# Motorsteuerung_V5.net
KiCad netlist of a schematic drawn in Altium Designer
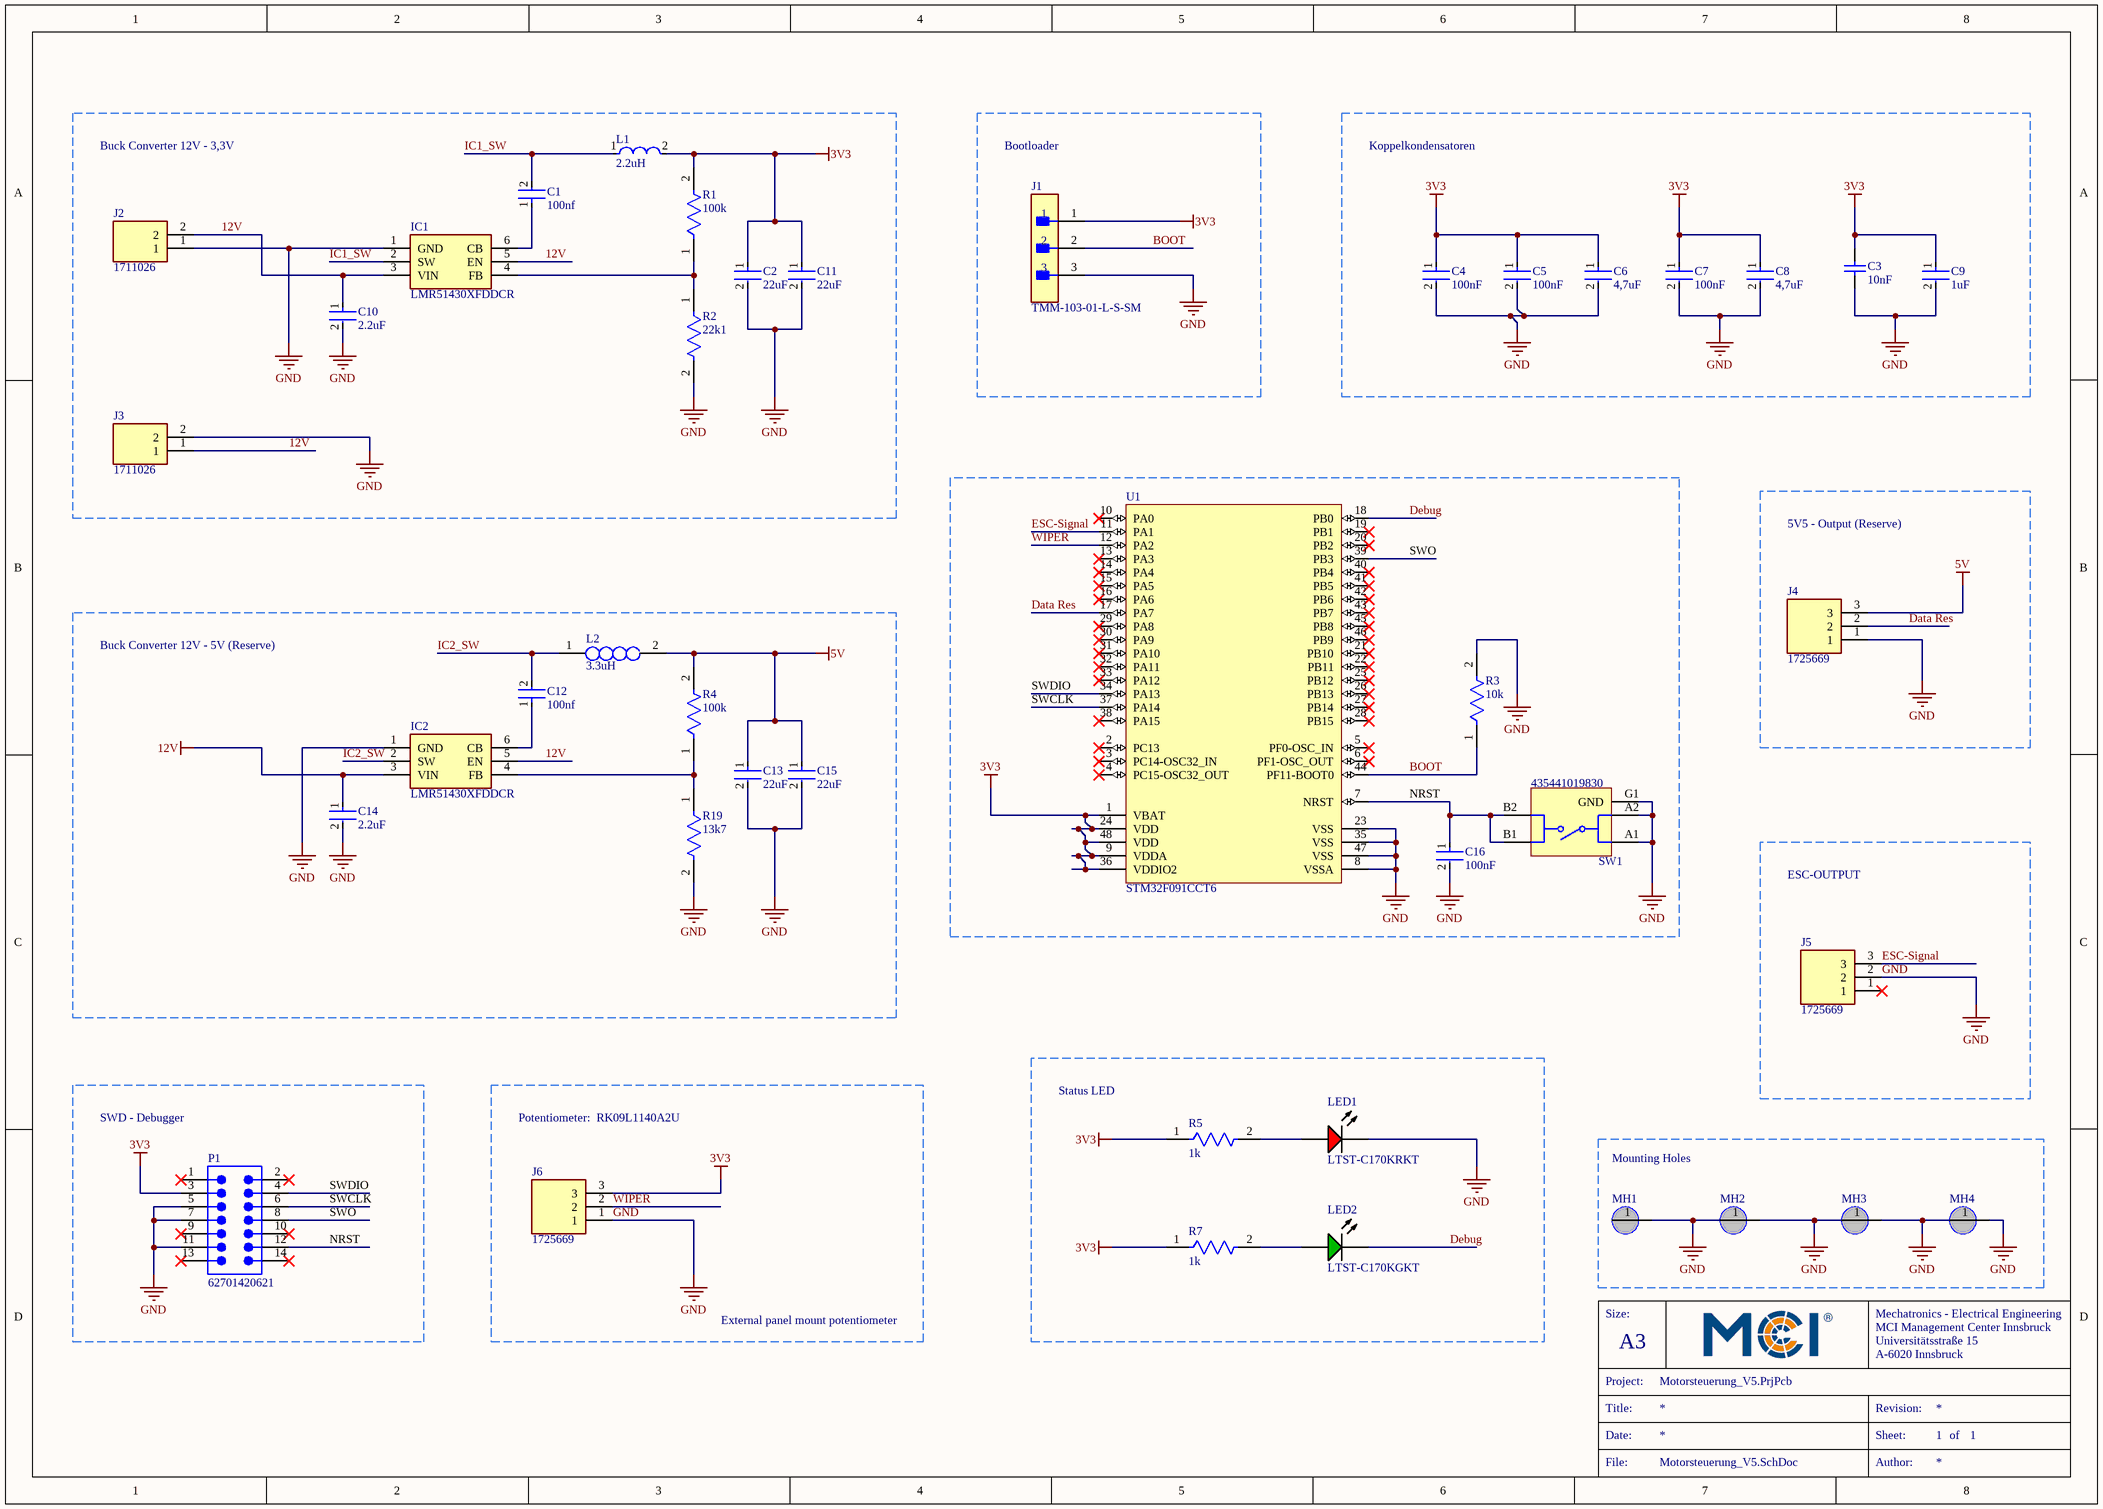
[diagram p0: Motorsteuerung_V5.SchDoc]

(export (version "E")
  (design (tool "Eeschema 10.0.6"))
  (components
    (comp (ref "C1")
      (value "100nf")
      (footprint "FP-C0805C104M5UACTU-MFG")
      (description "CAP CER 0.1UF 50V Z5U 0805")
      (fields (field (name "TOLERANCE") "20%") (field (name "VOLTAGE") "50V"))
      (libsource (lib "Altium Content Vault") (part "b4654b650e69147ec39a6b967a45e02"))
    )
    (comp (ref "C2")
      (value "22uF")
      (footprint "FP-C1210C226K4RACTU-MFG")
      (description "CAP CER 22UF 16V X7R 1210")
      (fields (field (name "VOLTAGE") "16V") (field (name "TOLERANCE") "10%"))
      (libsource (lib "Altium Content Vault") (part "b4654b650e69147ec39a6b967a45e02"))
    )
    (comp (ref "C3")
      (value "10nF")
      (footprint "CAPC1608X92X38ML15T08")
      (fields (field (name "MANUFACTURER") "Vitramon") (field (name "PART NUMBER") "VJ0603Y103KXJAC"))
      (libsource (lib "Altium Content Vault") (part "CAP"))
    )
    (comp (ref "C4")
      (value "100nF")
      (footprint "FP-CC0603-DA-MFG")
      (description "CAP CER 0.1UF 25V X7R 0603")
      (fields
        (field (name "MANUFACTURER") "YAGEO")
        (field (name "OCTOPART") "https://octopart.com/cc0603krx7r8bb104-yageo-8376534")
      )
      (libsource (lib "Altium Content Vault") (part "11868f565c42a9108669ba33697ecf6"))
    )
    (comp (ref "C5")
      (value "100nF")
      (footprint "FP-CC0603-DA-MFG")
      (description "CAP CER 0.1UF 25V X7R 0603")
      (fields
        (field (name "MANUFACTURER") "YAGEO")
        (field (name "OCTOPART") "https://octopart.com/cc0603krx7r8bb104-yageo-8376534")
      )
      (libsource (lib "Altium Content Vault") (part "11868f565c42a9108669ba33697ecf6"))
    )
    (comp (ref "C6")
      (value "4,7uF")
      (footprint "FP-CC0603-DA-MFG")
      (description "CAP CER 4.7UF 16V X5R 0603")
      (fields
        (field (name "MANUFACTURER") "YAGEO")
        (field (name "MANUFACTURER PART NUMBER") "CC0603KRX5R7BB475")
      )
      (libsource (lib "Altium Content Vault") (part "11868f565c42a9108669ba33697ecf6"))
    )
    (comp (ref "C7")
      (value "100nF")
      (footprint "FP-CC0603-DA-MFG")
      (description "CAP CER 0.1UF 25V X7R 0603")
      (fields
        (field (name "MANUFACTURER") "YAGEO")
        (field (name "OCTOPART") "https://octopart.com/cc0603krx7r8bb104-yageo-8376534")
      )
      (libsource (lib "Altium Content Vault") (part "11868f565c42a9108669ba33697ecf6"))
    )
    (comp (ref "C8")
      (value "4,7uF")
      (footprint "FP-CC0603-DA-MFG")
      (description "CAP CER 4.7UF 16V X5R 0603")
      (fields
        (field (name "MANUFACTURER") "YAGEO")
        (field (name "MANUFACTURER PART NUMBER") "CC0603KRX5R7BB475")
      )
      (libsource (lib "Altium Content Vault") (part "11868f565c42a9108669ba33697ecf6"))
    )
    (comp (ref "C9")
      (value "1uF")
      (footprint "FP-CC0603-DA-MFG")
      (description "CAP CER 1UF 16V X5R 0603")
      (fields
        (field (name "OCTOPART") "https://octopart.com/cc0603krx5r7bb105-yageo-8376530")
        (field (name "MANUFACTURER PART NUMBER") "CC0603KRX5R7BB105")
      )
      (libsource (lib "Altium Content Vault") (part "11868f565c42a9108669ba33697ecf6"))
    )
    (comp (ref "C10")
      (value "2.2uF")
      (footprint "FP-CC1210-G3-MFG")
      (description "CAP CER 1210")
      (fields (field (name "TOLERANCE") "10%"))
      (libsource (lib "Altium Content Vault") (part "b4654b650e69147ec39a6b967a45e02"))
    )
    (comp (ref "C11")
      (value "22uF")
      (footprint "FP-C1210C226K4RACTU-MFG")
      (description "CAP CER 22UF 16V X7R 1210")
      (fields (field (name "VOLTAGE") "16V") (field (name "TOLERANCE") "10%"))
      (libsource (lib "Altium Content Vault") (part "b4654b650e69147ec39a6b967a45e02"))
    )
    (comp (ref "C12")
      (value "100nf")
      (footprint "FP-C0805C104M5UACTU-MFG")
      (description "CAP CER 0.1UF 50V Z5U 0805")
      (fields (field (name "TOLERANCE") "20%") (field (name "VOLTAGE") "50V"))
      (libsource (lib "Altium Content Vault") (part "b4654b650e69147ec39a6b967a45e02"))
    )
    (comp (ref "C13")
      (value "22uF")
      (footprint "FP-C1210C226K4RACTU-MFG")
      (description "CAP CER 22UF 16V X7R 1210")
      (fields (field (name "VOLTAGE") "16V") (field (name "TOLERANCE") "10%"))
      (libsource (lib "Altium Content Vault") (part "b4654b650e69147ec39a6b967a45e02"))
    )
    (comp (ref "C14")
      (value "2.2uF")
      (footprint "FP-CC1210-G3-MFG")
      (description "CAP CER 1210")
      (fields (field (name "TOLERANCE") "10%"))
      (libsource (lib "Altium Content Vault") (part "b4654b650e69147ec39a6b967a45e02"))
    )
    (comp (ref "C15")
      (value "22uF")
      (footprint "FP-C1210C226K4RACTU-MFG")
      (description "CAP CER 22UF 16V X7R 1210")
      (fields (field (name "VOLTAGE") "16V") (field (name "TOLERANCE") "10%"))
      (libsource (lib "Altium Content Vault") (part "b4654b650e69147ec39a6b967a45e02"))
    )
    (comp (ref "C16")
      (value "100nF")
      (footprint "FP-CC0805-EB-MFG")
      (description "CC0805KKX7RYBB104 Capacitor Ceramic 0.01uF 250V X7R 10% 0805 T/R")
      (fields (field (name "TOLERANCE") "10%"))
      (libsource (lib "Altium Content Vault") (part "b4654b650e69147ec39a6b967a45e02"))
    )
    (comp (ref "IC1")
      (value "LMR51430XFDDCR")
      (footprint "SamacSys:SOT95P280X110-6N")
      (description "Integrated Circuit")
      (fields (field (name "MOUSER PART NUMBER") "595-LMR51430XFDDCR"))
      (libsource (lib "*") (part "LMR51430XFDDCR"))
    )
    (comp (ref "IC2")
      (value "LMR51430XFDDCR")
      (footprint "SamacSys:SOT95P280X110-6N")
      (description "Integrated Circuit")
      (fields (field (name "MOUSER PART NUMBER") "595-LMR51430XFDDCR"))
      (libsource (lib "*") (part "LMR51430XFDDCR"))
    )
    (comp (ref "J1")
      (value "TMM-103-01-L-S-SM")
      (footprint "FP-TMM-103-01-L-S-SM-MFG")
      (description "CONN HEADER SMD 3POS 2MM")
      (libsource (lib "Altium Content Vault") (part "0d3f023dd272f625e17a2be33dea85f"))
    )
    (comp (ref "J2")
      (value "1711026")
      (footprint "SamacSys:1711026")
      (description "Connector")
      (fields (field (name "MOUSER PART NUMBER") "651-1711026"))
      (libsource (lib "*") (part "1711026"))
    )
    (comp (ref "J3")
      (value "1711026")
      (footprint "SamacSys:1711026")
      (description "Connector")
      (fields (field (name "MOUSER PART NUMBER") "651-1711026"))
      (libsource (lib "*") (part "1711026"))
    )
    (comp (ref "J4")
      (value "1725669")
      (footprint "SamacSys:1725669")
      (description "Connector")
      (fields (field (name "MOUSER PART NUMBER") "651-1725669"))
      (libsource (lib "Motorsteuerung_V5") (part "1725669"))
    )
    (comp (ref "J5")
      (value "1725669")
      (footprint "SamacSys:1725669")
      (description "Connector")
      (fields (field (name "MOUSER PART NUMBER") "651-1725669"))
      (libsource (lib "Motorsteuerung_V5") (part "1725669"))
    )
    (comp (ref "J6")
      (value "1725669")
      (footprint "SamacSys:1725669")
      (description "Connector")
      (fields (field (name "MOUSER PART NUMBER") "651-1725669"))
      (libsource (lib "Motorsteuerung_V5") (part "1725669"))
    )
    (comp (ref "L1")
      (value "2.2uH")
      (footprint "FP-IHLP-2020BZ-FP_1_905x2-MFG")
      (description "Fixed Inductors Commercial Low DCR Series 2.2uH 5A 37.7mΩ 20%")
      (fields (field (name "TOLERANCE") "20%"))
      (libsource (lib "Altium Content Vault") (part "725321dda6339637d4d059423bc1c3c"))
    )
    (comp (ref "L2")
      (value "3.3uH")
      (footprint "SamacSys:INDPM6054X300N")
      (description "Inductor")
      (fields
        (field (name "MANUFACTURER_PART_NUMBER") "PA4340.332NLT")
        (field (name "MOUSER PART NUMBER") "673-PA4340.332NLT")
      )
      (libsource (lib "*") (part "PA4340.332NLT"))
    )
    (comp (ref "LED1")
      (value "LTST-C170KRKT")
      (footprint "LTST-C170KRKT_V")
      (description "LED Red, 75 mW, 54 mcd, -55 to 85 degC, 2-Pin SMD, RoHS, Tape and Reel")
      (fields (field (name "MANUFACTURER") "Lite-On"))
      (libsource (lib "Altium Content Vault") (part "LED-RED-AK-2"))
    )
    (comp (ref "LED2")
      (value "LTST-C170KGKT")
      (footprint "LTST-LTST-C170KGKT-2_V")
      (description "Ultra Bright AlInGaP Chip LED, 75 mW, -55 to 85 degC, 2-Pin SMD (0805), RoHS, Tape and Reel")
      (fields (field (name "MANUFACTURER") "Lite-On"))
      (libsource (lib "Altium Content Vault") (part "LED-GREEN-KA-2"))
    )
    (comp (ref "MH1")
      (value "MountingHole")
      (footprint "MTH")
      (libsource (lib "Motorsteuerung_V5") (part "MountingHole"))
    )
    (comp (ref "MH2")
      (value "MountingHole")
      (footprint "MTH")
      (libsource (lib "Motorsteuerung_V5") (part "MountingHole"))
    )
    (comp (ref "MH3")
      (value "MountingHole")
      (footprint "MTH")
      (libsource (lib "Motorsteuerung_V5") (part "MountingHole"))
    )
    (comp (ref "MH4")
      (value "MountingHole")
      (footprint "MTH")
      (libsource (lib "Motorsteuerung_V5") (part "MountingHole"))
    )
    (comp (ref "P1")
      (value "62701420621")
      (footprint "62701420621")
      (description "Conn, Hdr, 14Pos, 2Row, 1.27Mm, Smt Rohs Compliant: Yes")
      (libsource (lib "Altium Content Vault") (part "Header_Male_2R_14P"))
    )
    (comp (ref "R1")
      (value "100k")
      (footprint "FP-RQ73C2A-IPC_B")
      (description "RQ73 0805 100KΩ 0.2W 10ppm/°C 0.1% 100V")
      (libsource (lib "Altium Content Vault") (part "1029c3af85768c4190bb7ad29bc67b5"))
    )
    (comp (ref "R2")
      (value "22k1")
      (footprint "FP-RT0805-MFG")
      (description "RES SMD 22.1K OHM 0.1% 1/8W 0805")
      (fields
        (field (name "MANUFACTURER PART NUMBER") "RT0805BRD0722K1L")
        (field (name "MANUFACTURER") "Yageo")
      )
      (libsource (lib "Altium Content Vault") (part "1029c3af85768c4190bb7ad29bc67b5"))
    )
    (comp (ref "R3")
      (value "10k")
      (footprint "FP-CRGCQ0805-IPC_C")
      (description "CRGCQ 0805 10K 5%")
      (fields
        (field (name "MANUFACTURER PART NUMBER") "CRGCQ0805J10K")
        (field (name "MANUFACTURER") "TE Connectivity")
      )
      (libsource (lib "Altium Content Vault") (part "1029c3af85768c4190bb7ad29bc67b5"))
    )
    (comp (ref "R4")
      (value "100k")
      (footprint "FP-RQ73C2A-IPC_B")
      (description "RQ73 0805 100KΩ 0.2W 10ppm/°C 0.1% 100V")
      (libsource (lib "Altium Content Vault") (part "1029c3af85768c4190bb7ad29bc67b5"))
    )
    (comp (ref "R5")
      (value "1k")
      (footprint "FP-CRGCQ0805-IPC_C")
      (description "CRGCQ 0805 1K0 1%")
      (fields
        (field (name "OCTOPART") "https://octopart.com/crgcq0805f1k0-te+connectivity-91018154")
        (field (name "MANUFACTURER") "TE Connectivity")
      )
      (libsource (lib "Altium Content Vault") (part "1029c3af85768c4190bb7ad29bc67b5"))
    )
    (comp (ref "R7")
      (value "1k")
      (footprint "FP-CRGCQ0805-IPC_C")
      (description "CRGCQ 0805 1K0 1%")
      (fields
        (field (name "OCTOPART") "https://octopart.com/crgcq0805f1k0-te+connectivity-91018154")
        (field (name "MANUFACTURER") "TE Connectivity")
      )
      (libsource (lib "Altium Content Vault") (part "1029c3af85768c4190bb7ad29bc67b5"))
    )
    (comp (ref "R19")
      (value "13k7")
      (footprint "FP-RT0805-MFG")
      (description "RES 13.7K OHM 1/8W .1% SMD 0805")
      (fields
        (field (name "MANUFACTURER PART NUMBER") "RT0805BRD0713K7L")
        (field (name "MANUFACTURER") "Yageo")
      )
      (libsource (lib "Altium Content Vault") (part "1029c3af85768c4190bb7ad29bc67b5"))
    )
    (comp (ref "SW1")
      (value "435441019830")
      (footprint "435441019830")
      (description "Tactile Switch, 0.05A, 32Vdc, Smd, 300Gf Rohs Compliant: Yes")
      (libsource (lib "Altium Content Vault") (part "SPST-NO_4P_1GND"))
    )
    (comp (ref "U1")
      (value "STM32F091CCT6")
      (footprint "LQFP48_M")
      (fields (field (name "MANUFACTURER") "STMicroelectronics"))
      (libsource (lib "Altium Content Vault") (part "STM-STM32F091C-LQFP-48"))
    )
  )
  (nets
    (net (code "1") (name "/BOOT") (class "Default")
      (node (ref "J1") (pin "2") (pinfunction "2_2") (pintype "passive"))
      (node (ref "R3") (pin "1") (pinfunction "1_1") (pintype "passive"))
      (node (ref "U1") (pin "44") (pinfunction "PF11-BOOT0_44") (pintype "bidirectional"))
    )
    (net (code "2") (name "/Data Res") (class "Default")
      (node (ref "J4") (pin "2") (pinfunction "2_2") (pintype "passive"))
      (node (ref "U1") (pin "17") (pinfunction "PA7_17") (pintype "bidirectional"))
    )
    (net (code "3") (name "/Debug") (class "Default")
      (node (ref "LED2") (pin "1") (pinfunction "K_1") (pintype "passive"))
      (node (ref "U1") (pin "18") (pinfunction "PB0_18") (pintype "bidirectional"))
    )
    (net (code "4") (name "/ESC-Signal") (class "Default")
      (node (ref "J5") (pin "3") (pinfunction "3_3") (pintype "passive"))
      (node (ref "U1") (pin "11") (pinfunction "PA1_11") (pintype "bidirectional"))
    )
    (net (code "5") (name "/IC1_SW") (class "Default")
      (node (ref "C1") (pin "2") (pinfunction "2_2") (pintype "passive"))
      (node (ref "IC1") (pin "2") (pinfunction "SW_2") (pintype "passive"))
      (node (ref "L1") (pin "1") (pinfunction "1_1") (pintype "passive"))
    )
    (net (code "6") (name "/IC2_SW") (class "Default")
      (node (ref "C12") (pin "2") (pinfunction "2_2") (pintype "passive"))
      (node (ref "IC2") (pin "2") (pinfunction "SW_2") (pintype "passive"))
      (node (ref "L2") (pin "1") (pinfunction "1_1") (pintype "passive"))
    )
    (net (code "7") (name "/NRST") (class "Default")
      (node (ref "C16") (pin "1") (pinfunction "1_1") (pintype "passive"))
      (node (ref "P1") (pin "12") (pinfunction "12_12") (pintype "passive"))
      (node (ref "SW1") (pin "B1") (pinfunction "B1_B1") (pintype "passive"))
      (node (ref "SW1") (pin "B2") (pinfunction "B2_B2") (pintype "passive"))
      (node (ref "U1") (pin "7") (pinfunction "NRST_7") (pintype "bidirectional"))
    )
    (net (code "8") (name "/SWCLK") (class "Default")
      (node (ref "P1") (pin "6") (pinfunction "6_6") (pintype "passive"))
      (node (ref "U1") (pin "37") (pinfunction "PA14_37") (pintype "bidirectional"))
    )
    (net (code "9") (name "/SWDIO") (class "Default")
      (node (ref "P1") (pin "4") (pinfunction "4_4") (pintype "passive"))
      (node (ref "U1") (pin "34") (pinfunction "PA13_34") (pintype "bidirectional"))
    )
    (net (code "10") (name "/SWO") (class "Default")
      (node (ref "P1") (pin "8") (pinfunction "8_8") (pintype "passive"))
      (node (ref "U1") (pin "39") (pinfunction "PB3_39") (pintype "bidirectional"))
    )
    (net (code "11") (name "/WIPER") (class "Default")
      (node (ref "J6") (pin "2") (pinfunction "2_2") (pintype "passive"))
      (node (ref "U1") (pin "12") (pinfunction "PA2_12") (pintype "bidirectional"))
    )
    (net (code "12") (name "3V3") (class "Default")
      (node (ref "C11") (pin "1") (pinfunction "1_1") (pintype "passive"))
      (node (ref "C2") (pin "1") (pinfunction "1_1") (pintype "passive"))
      (node (ref "C3") (pin "2") (pinfunction "2_2") (pintype "passive"))
      (node (ref "C4") (pin "1") (pinfunction "1_1") (pintype "passive"))
      (node (ref "C5") (pin "1") (pinfunction "1_1") (pintype "passive"))
      (node (ref "C6") (pin "1") (pinfunction "1_1") (pintype "passive"))
      (node (ref "C7") (pin "1") (pinfunction "1_1") (pintype "passive"))
      (node (ref "C8") (pin "1") (pinfunction "1_1") (pintype "passive"))
      (node (ref "C9") (pin "1") (pinfunction "1_1") (pintype "passive"))
      (node (ref "J1") (pin "1") (pinfunction "1_1") (pintype "passive"))
      (node (ref "J6") (pin "3") (pinfunction "3_3") (pintype "passive"))
      (node (ref "L1") (pin "2") (pinfunction "2_2") (pintype "passive"))
      (node (ref "P1") (pin "3") (pinfunction "3_3") (pintype "passive"))
      (node (ref "R1") (pin "2") (pinfunction "2_2") (pintype "passive"))
      (node (ref "R5") (pin "1") (pinfunction "1_1") (pintype "passive"))
      (node (ref "R7") (pin "1") (pinfunction "1_1") (pintype "passive"))
      (node (ref "U1") (pin "1") (pinfunction "VBAT_1") (pintype "power_in"))
      (node (ref "U1") (pin "24") (pinfunction "VDD_24") (pintype "power_in"))
      (node (ref "U1") (pin "36") (pinfunction "VDDIO2_36") (pintype "power_in"))
      (node (ref "U1") (pin "48") (pinfunction "VDD_48") (pintype "power_in"))
      (node (ref "U1") (pin "9") (pinfunction "VDDA_9") (pintype "power_in"))
    )
    (net (code "13") (name "5V") (class "Default")
      (node (ref "C13") (pin "1") (pinfunction "1_1") (pintype "passive"))
      (node (ref "C15") (pin "1") (pinfunction "1_1") (pintype "passive"))
      (node (ref "J4") (pin "3") (pinfunction "3_3") (pintype "passive"))
      (node (ref "L2") (pin "2") (pinfunction "2_2") (pintype "passive"))
      (node (ref "R4") (pin "2") (pinfunction "2_2") (pintype "passive"))
    )
    (net (code "14") (name "12V") (class "Default")
      (node (ref "C10") (pin "1") (pinfunction "1_1") (pintype "passive"))
      (node (ref "C14") (pin "1") (pinfunction "1_1") (pintype "passive"))
      (node (ref "IC1") (pin "3") (pinfunction "VIN_3") (pintype "passive"))
      (node (ref "IC1") (pin "5") (pinfunction "EN_5") (pintype "passive"))
      (node (ref "IC2") (pin "3") (pinfunction "VIN_3") (pintype "passive"))
      (node (ref "IC2") (pin "5") (pinfunction "EN_5") (pintype "passive"))
      (node (ref "J2") (pin "2") (pinfunction "2_2") (pintype "passive"))
      (node (ref "J3") (pin "1") (pinfunction "1_1") (pintype "passive"))
    )
    (net (code "15") (name "GND") (class "Default")
      (node (ref "C10") (pin "2") (pinfunction "2_2") (pintype "passive"))
      (node (ref "C11") (pin "2") (pinfunction "2_2") (pintype "passive"))
      (node (ref "C13") (pin "2") (pinfunction "2_2") (pintype "passive"))
      (node (ref "C14") (pin "2") (pinfunction "2_2") (pintype "passive"))
      (node (ref "C15") (pin "2") (pinfunction "2_2") (pintype "passive"))
      (node (ref "C16") (pin "2") (pinfunction "2_2") (pintype "passive"))
      (node (ref "C2") (pin "2") (pinfunction "2_2") (pintype "passive"))
      (node (ref "C3") (pin "1") (pinfunction "1_1") (pintype "passive"))
      (node (ref "C4") (pin "2") (pinfunction "2_2") (pintype "passive"))
      (node (ref "C5") (pin "2") (pinfunction "2_2") (pintype "passive"))
      (node (ref "C6") (pin "2") (pinfunction "2_2") (pintype "passive"))
      (node (ref "C7") (pin "2") (pinfunction "2_2") (pintype "passive"))
      (node (ref "C8") (pin "2") (pinfunction "2_2") (pintype "passive"))
      (node (ref "C9") (pin "2") (pinfunction "2_2") (pintype "passive"))
      (node (ref "IC1") (pin "1") (pinfunction "GND_1") (pintype "passive"))
      (node (ref "IC2") (pin "1") (pinfunction "GND_1") (pintype "passive"))
      (node (ref "J1") (pin "3") (pinfunction "3_3") (pintype "passive"))
      (node (ref "J2") (pin "1") (pinfunction "1_1") (pintype "passive"))
      (node (ref "J3") (pin "2") (pinfunction "2_2") (pintype "passive"))
      (node (ref "J4") (pin "1") (pinfunction "1_1") (pintype "passive"))
      (node (ref "J5") (pin "2") (pinfunction "2_2") (pintype "passive"))
      (node (ref "J6") (pin "1") (pinfunction "1_1") (pintype "passive"))
      (node (ref "LED1") (pin "2") (pinfunction "K_2") (pintype "passive"))
      (node (ref "MH1") (pin "1") (pintype "passive"))
      (node (ref "MH2") (pin "1") (pintype "passive"))
      (node (ref "MH3") (pin "1") (pintype "passive"))
      (node (ref "MH4") (pin "1") (pintype "passive"))
      (node (ref "P1") (pin "11") (pinfunction "11_11") (pintype "passive"))
      (node (ref "P1") (pin "5") (pinfunction "5_5") (pintype "passive"))
      (node (ref "P1") (pin "7") (pinfunction "7_7") (pintype "passive"))
      (node (ref "R19") (pin "2") (pinfunction "2_2") (pintype "passive"))
      (node (ref "R2") (pin "2") (pinfunction "2_2") (pintype "passive"))
      (node (ref "R3") (pin "2") (pinfunction "2_2") (pintype "passive"))
      (node (ref "SW1") (pin "A1") (pinfunction "A1_A1") (pintype "passive"))
      (node (ref "SW1") (pin "A2") (pinfunction "A2_A2") (pintype "passive"))
      (node (ref "SW1") (pin "G1") (pinfunction "GND_G1") (pintype "passive"))
      (node (ref "U1") (pin "23") (pinfunction "VSS_23") (pintype "power_in"))
      (node (ref "U1") (pin "35") (pinfunction "VSS_35") (pintype "power_in"))
      (node (ref "U1") (pin "47") (pinfunction "VSS_47") (pintype "power_in"))
      (node (ref "U1") (pin "8") (pinfunction "VSSA_8") (pintype "power_in"))
    )
    (net (code "16") (name "Net-(IC1-CB)") (class "Default")
      (node (ref "C1") (pin "1") (pinfunction "1_1") (pintype "passive"))
      (node (ref "IC1") (pin "6") (pinfunction "CB_6") (pintype "passive"))
    )
    (net (code "17") (name "Net-(IC1-FB)") (class "Default")
      (node (ref "IC1") (pin "4") (pinfunction "FB_4") (pintype "passive"))
      (node (ref "R1") (pin "1") (pinfunction "1_1") (pintype "passive"))
      (node (ref "R2") (pin "1") (pinfunction "1_1") (pintype "passive"))
    )
    (net (code "18") (name "Net-(IC2-CB)") (class "Default")
      (node (ref "C12") (pin "1") (pinfunction "1_1") (pintype "passive"))
      (node (ref "IC2") (pin "6") (pinfunction "CB_6") (pintype "passive"))
    )
    (net (code "19") (name "Net-(IC2-FB)") (class "Default")
      (node (ref "IC2") (pin "4") (pinfunction "FB_4") (pintype "passive"))
      (node (ref "R19") (pin "1") (pinfunction "1_1") (pintype "passive"))
      (node (ref "R4") (pin "1") (pinfunction "1_1") (pintype "passive"))
    )
    (net (code "20") (name "Net-(LED1-A)") (class "Default")
      (node (ref "LED1") (pin "1") (pinfunction "A_1") (pintype "passive"))
      (node (ref "R5") (pin "2") (pinfunction "2_2") (pintype "passive"))
    )
    (net (code "21") (name "Net-(LED2-A)") (class "Default")
      (node (ref "LED2") (pin "2") (pinfunction "A_2") (pintype "passive"))
      (node (ref "R7") (pin "2") (pinfunction "2_2") (pintype "passive"))
    )
    (net (code "22") (name "unconnected-(J5-Pad1)") (class "Default")
      (node (ref "J5") (pin "1") (pinfunction "1_1") (pintype "passive+no_connect"))
    )
    (net (code "23") (name "unconnected-(P1-Pad1)") (class "Default")
      (node (ref "P1") (pin "1") (pinfunction "1_1") (pintype "passive+no_connect"))
    )
    (net (code "24") (name "unconnected-(P1-Pad2)") (class "Default")
      (node (ref "P1") (pin "2") (pinfunction "2_2") (pintype "passive+no_connect"))
    )
    (net (code "25") (name "unconnected-(P1-Pad9)") (class "Default")
      (node (ref "P1") (pin "9") (pinfunction "9_9") (pintype "passive+no_connect"))
    )
    (net (code "26") (name "unconnected-(P1-Pad10)") (class "Default")
      (node (ref "P1") (pin "10") (pinfunction "10_10") (pintype "passive+no_connect"))
    )
    (net (code "27") (name "unconnected-(P1-Pad13)") (class "Default")
      (node (ref "P1") (pin "13") (pinfunction "13_13") (pintype "passive+no_connect"))
    )
    (net (code "28") (name "unconnected-(P1-Pad14)") (class "Default")
      (node (ref "P1") (pin "14") (pinfunction "14_14") (pintype "passive+no_connect"))
    )
    (net (code "29") (name "unconnected-(U1-PA0-Pad10)") (class "Default")
      (node (ref "U1") (pin "10") (pinfunction "PA0_10") (pintype "bidirectional+no_connect"))
    )
    (net (code "30") (name "unconnected-(U1-PA3-Pad13)") (class "Default")
      (node (ref "U1") (pin "13") (pinfunction "PA3_13") (pintype "bidirectional+no_connect"))
    )
    (net (code "31") (name "unconnected-(U1-PA4-Pad14)") (class "Default")
      (node (ref "U1") (pin "14") (pinfunction "PA4_14") (pintype "bidirectional+no_connect"))
    )
    (net (code "32") (name "unconnected-(U1-PA5-Pad15)") (class "Default")
      (node (ref "U1") (pin "15") (pinfunction "PA5_15") (pintype "bidirectional+no_connect"))
    )
    (net (code "33") (name "unconnected-(U1-PA6-Pad16)") (class "Default")
      (node (ref "U1") (pin "16") (pinfunction "PA6_16") (pintype "bidirectional+no_connect"))
    )
    (net (code "34") (name "unconnected-(U1-PA8-Pad29)") (class "Default")
      (node (ref "U1") (pin "29") (pinfunction "PA8_29") (pintype "bidirectional+no_connect"))
    )
    (net (code "35") (name "unconnected-(U1-PA9-Pad30)") (class "Default")
      (node (ref "U1") (pin "30") (pinfunction "PA9_30") (pintype "bidirectional+no_connect"))
    )
    (net (code "36") (name "unconnected-(U1-PA10-Pad31)") (class "Default")
      (node (ref "U1") (pin "31") (pinfunction "PA10_31") (pintype "bidirectional+no_connect"))
    )
    (net (code "37") (name "unconnected-(U1-PA11-Pad32)") (class "Default")
      (node (ref "U1") (pin "32") (pinfunction "PA11_32") (pintype "bidirectional+no_connect"))
    )
    (net (code "38") (name "unconnected-(U1-PA12-Pad33)") (class "Default")
      (node (ref "U1") (pin "33") (pinfunction "PA12_33") (pintype "bidirectional+no_connect"))
    )
    (net (code "39") (name "unconnected-(U1-PA15-Pad38)") (class "Default")
      (node (ref "U1") (pin "38") (pinfunction "PA15_38") (pintype "bidirectional+no_connect"))
    )
    (net (code "40") (name "unconnected-(U1-PB1-Pad19)") (class "Default")
      (node (ref "U1") (pin "19") (pinfunction "PB1_19") (pintype "bidirectional+no_connect"))
    )
    (net (code "41") (name "unconnected-(U1-PB2-Pad20)") (class "Default")
      (node (ref "U1") (pin "20") (pinfunction "PB2_20") (pintype "bidirectional+no_connect"))
    )
    (net (code "42") (name "unconnected-(U1-PB4-Pad40)") (class "Default")
      (node (ref "U1") (pin "40") (pinfunction "PB4_40") (pintype "bidirectional+no_connect"))
    )
    (net (code "43") (name "unconnected-(U1-PB5-Pad41)") (class "Default")
      (node (ref "U1") (pin "41") (pinfunction "PB5_41") (pintype "bidirectional+no_connect"))
    )
    (net (code "44") (name "unconnected-(U1-PB6-Pad42)") (class "Default")
      (node (ref "U1") (pin "42") (pinfunction "PB6_42") (pintype "bidirectional+no_connect"))
    )
    (net (code "45") (name "unconnected-(U1-PB7-Pad43)") (class "Default")
      (node (ref "U1") (pin "43") (pinfunction "PB7_43") (pintype "bidirectional+no_connect"))
    )
    (net (code "46") (name "unconnected-(U1-PB8-Pad45)") (class "Default")
      (node (ref "U1") (pin "45") (pinfunction "PB8_45") (pintype "bidirectional+no_connect"))
    )
    (net (code "47") (name "unconnected-(U1-PB9-Pad46)") (class "Default")
      (node (ref "U1") (pin "46") (pinfunction "PB9_46") (pintype "bidirectional+no_connect"))
    )
    (net (code "48") (name "unconnected-(U1-PB10-Pad21)") (class "Default")
      (node (ref "U1") (pin "21") (pinfunction "PB10_21") (pintype "bidirectional+no_connect"))
    )
    (net (code "49") (name "unconnected-(U1-PB11-Pad22)") (class "Default")
      (node (ref "U1") (pin "22") (pinfunction "PB11_22") (pintype "bidirectional+no_connect"))
    )
    (net (code "50") (name "unconnected-(U1-PB12-Pad25)") (class "Default")
      (node (ref "U1") (pin "25") (pinfunction "PB12_25") (pintype "bidirectional+no_connect"))
    )
    (net (code "51") (name "unconnected-(U1-PB13-Pad26)") (class "Default")
      (node (ref "U1") (pin "26") (pinfunction "PB13_26") (pintype "bidirectional+no_connect"))
    )
    (net (code "52") (name "unconnected-(U1-PB14-Pad27)") (class "Default")
      (node (ref "U1") (pin "27") (pinfunction "PB14_27") (pintype "bidirectional+no_connect"))
    )
    (net (code "53") (name "unconnected-(U1-PB15-Pad28)") (class "Default")
      (node (ref "U1") (pin "28") (pinfunction "PB15_28") (pintype "bidirectional+no_connect"))
    )
    (net (code "54") (name "unconnected-(U1-PC13-Pad2)") (class "Default")
      (node (ref "U1") (pin "2") (pinfunction "PC13_2") (pintype "bidirectional+no_connect"))
    )
    (net (code "55") (name "unconnected-(U1-PC14-OSC32_IN-Pad3)") (class "Default")
      (node (ref "U1") (pin "3") (pinfunction "PC14-OSC32_IN_3") (pintype "bidirectional+no_connect"))
    )
    (net (code "56") (name "unconnected-(U1-PC15-OSC32_OUT-Pad4)") (class "Default")
      (node (ref "U1") (pin "4") (pinfunction "PC15-OSC32_OUT_4") (pintype "bidirectional+no_connect"))
    )
    (net (code "57") (name "unconnected-(U1-PF0-OSC_IN-Pad5)") (class "Default")
      (node (ref "U1") (pin "5") (pinfunction "PF0-OSC_IN_5") (pintype "bidirectional+no_connect"))
    )
    (net (code "58") (name "unconnected-(U1-PF1-OSC_OUT-Pad6)") (class "Default")
      (node (ref "U1") (pin "6") (pinfunction "PF1-OSC_OUT_6") (pintype "bidirectional+no_connect"))
    )
  )
)
